# TransistorsArduino.net
KiCad netlist of a schematic drawn in EAGLE
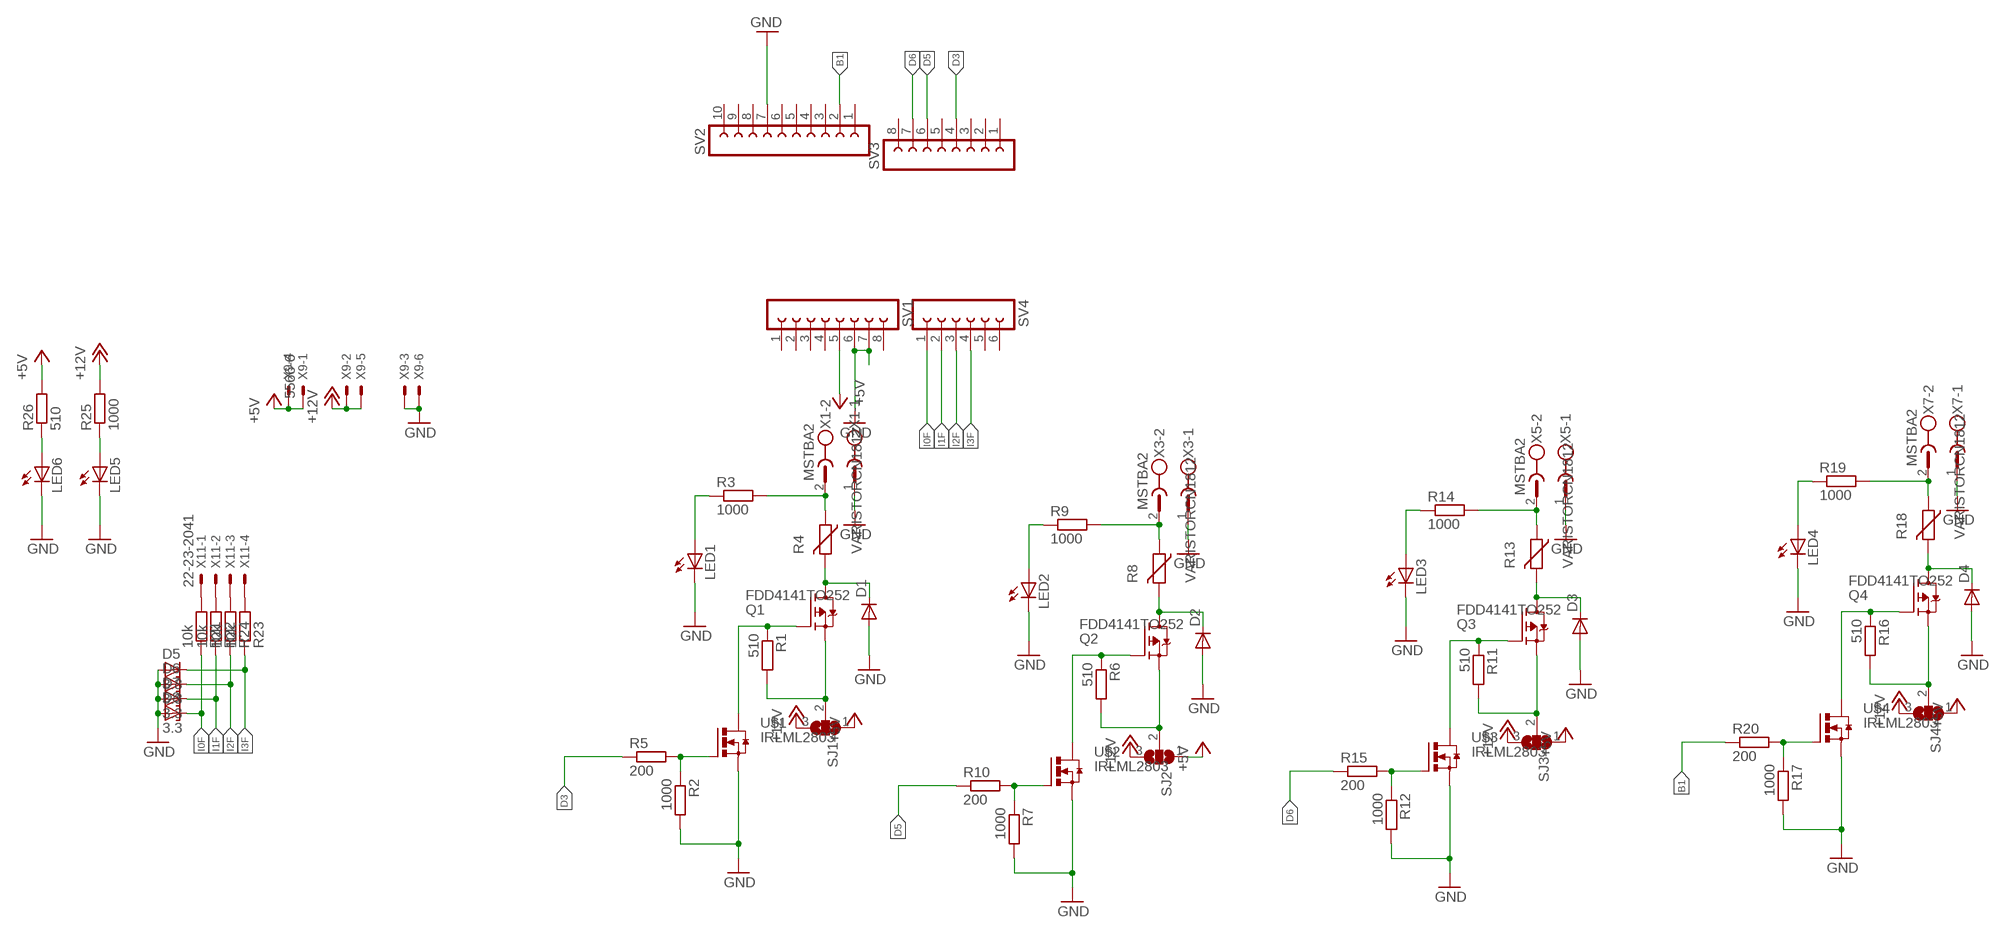
[diagram p0: schematic, sheet 1]

(export (version "E")
  (design (tool "Eeschema 10.0.6"))
  (components
    (comp (ref "D1")
      (value "DIODE-SMB")
      (footprint "eagle-import:SMB")
      (libsource (lib "eagle-import") (part "DIODE-SMB"))
    )
    (comp (ref "D2")
      (value "DIODE-SMB")
      (footprint "eagle-import:SMB")
      (libsource (lib "eagle-import") (part "DIODE-SMB"))
    )
    (comp (ref "D3")
      (value "DIODE-SMB")
      (footprint "eagle-import:SMB")
      (libsource (lib "eagle-import") (part "DIODE-SMB"))
    )
    (comp (ref "D4")
      (value "DIODE-SMB")
      (footprint "eagle-import:SMB")
      (libsource (lib "eagle-import") (part "DIODE-SMB"))
    )
    (comp (ref "D5")
      (value "3.3")
      (footprint "eagle-import:SOD80C")
      (libsource (lib "eagle-import") (part "ZENER-DIODESOD80C"))
    )
    (comp (ref "D6")
      (value "3.3")
      (footprint "eagle-import:SOD80C")
      (libsource (lib "eagle-import") (part "ZENER-DIODESOD80C"))
    )
    (comp (ref "D7")
      (value "3.3")
      (footprint "eagle-import:SOD80C")
      (libsource (lib "eagle-import") (part "ZENER-DIODESOD80C"))
    )
    (comp (ref "D8")
      (value "3.3")
      (footprint "eagle-import:SOD80C")
      (libsource (lib "eagle-import") (part "ZENER-DIODESOD80C"))
    )
    (comp (ref "LED1")
      (value "LEDCHIPLED_1206")
      (footprint "eagle-import:CHIPLED_1206")
      (libsource (lib "eagle-import") (part "LEDCHIPLED_1206"))
    )
    (comp (ref "LED2")
      (value "LEDCHIPLED_1206")
      (footprint "eagle-import:CHIPLED_1206")
      (libsource (lib "eagle-import") (part "LEDCHIPLED_1206"))
    )
    (comp (ref "LED3")
      (value "LEDCHIPLED_1206")
      (footprint "eagle-import:CHIPLED_1206")
      (libsource (lib "eagle-import") (part "LEDCHIPLED_1206"))
    )
    (comp (ref "LED4")
      (value "LEDCHIPLED_1206")
      (footprint "eagle-import:CHIPLED_1206")
      (libsource (lib "eagle-import") (part "LEDCHIPLED_1206"))
    )
    (comp (ref "LED5")
      (value "LEDCHIPLED_1206")
      (footprint "eagle-import:CHIPLED_1206")
      (libsource (lib "eagle-import") (part "LEDCHIPLED_1206"))
    )
    (comp (ref "LED6")
      (value "LEDCHIPLED_1206")
      (footprint "eagle-import:CHIPLED_1206")
      (libsource (lib "eagle-import") (part "LEDCHIPLED_1206"))
    )
    (comp (ref "Q1")
      (value "FDD4141TO252")
      (footprint "eagle-import:TO252")
      (libsource (lib "eagle-import") (part "FDD4141TO252"))
    )
    (comp (ref "Q2")
      (value "FDD4141TO252")
      (footprint "eagle-import:TO252")
      (libsource (lib "eagle-import") (part "FDD4141TO252"))
    )
    (comp (ref "Q3")
      (value "FDD4141TO252")
      (footprint "eagle-import:TO252")
      (libsource (lib "eagle-import") (part "FDD4141TO252"))
    )
    (comp (ref "Q4")
      (value "FDD4141TO252")
      (footprint "eagle-import:TO252")
      (libsource (lib "eagle-import") (part "FDD4141TO252"))
    )
    (comp (ref "R1")
      (value "510")
      (footprint "eagle-import:M0805")
      (libsource (lib "eagle-import") (part "R-EU_M0805"))
    )
    (comp (ref "R2")
      (value "1000")
      (footprint "eagle-import:M0805")
      (libsource (lib "eagle-import") (part "R-EU_M0805"))
    )
    (comp (ref "R3")
      (value "1000")
      (footprint "eagle-import:M0805")
      (libsource (lib "eagle-import") (part "R-EU_M0805"))
    )
    (comp (ref "R4")
      (value "VARISTORCN1812")
      (footprint "eagle-import:CT_CN1812")
      (libsource (lib "eagle-import") (part "VARISTORCN1812"))
    )
    (comp (ref "R5")
      (value "200")
      (footprint "eagle-import:M0805")
      (libsource (lib "eagle-import") (part "R-EU_M0805"))
    )
    (comp (ref "R6")
      (value "510")
      (footprint "eagle-import:M0805")
      (libsource (lib "eagle-import") (part "R-EU_M0805"))
    )
    (comp (ref "R7")
      (value "1000")
      (footprint "eagle-import:M0805")
      (libsource (lib "eagle-import") (part "R-EU_M0805"))
    )
    (comp (ref "R8")
      (value "VARISTORCN1812")
      (footprint "eagle-import:CT_CN1812")
      (libsource (lib "eagle-import") (part "VARISTORCN1812"))
    )
    (comp (ref "R9")
      (value "1000")
      (footprint "eagle-import:M0805")
      (libsource (lib "eagle-import") (part "R-EU_M0805"))
    )
    (comp (ref "R10")
      (value "200")
      (footprint "eagle-import:M0805")
      (libsource (lib "eagle-import") (part "R-EU_M0805"))
    )
    (comp (ref "R11")
      (value "510")
      (footprint "eagle-import:M0805")
      (libsource (lib "eagle-import") (part "R-EU_M0805"))
    )
    (comp (ref "R12")
      (value "1000")
      (footprint "eagle-import:M0805")
      (libsource (lib "eagle-import") (part "R-EU_M0805"))
    )
    (comp (ref "R13")
      (value "VARISTORCN1812")
      (footprint "eagle-import:CT_CN1812")
      (libsource (lib "eagle-import") (part "VARISTORCN1812"))
    )
    (comp (ref "R14")
      (value "1000")
      (footprint "eagle-import:M0805")
      (libsource (lib "eagle-import") (part "R-EU_M0805"))
    )
    (comp (ref "R15")
      (value "200")
      (footprint "eagle-import:M0805")
      (libsource (lib "eagle-import") (part "R-EU_M0805"))
    )
    (comp (ref "R16")
      (value "510")
      (footprint "eagle-import:M0805")
      (libsource (lib "eagle-import") (part "R-EU_M0805"))
    )
    (comp (ref "R17")
      (value "1000")
      (footprint "eagle-import:M0805")
      (libsource (lib "eagle-import") (part "R-EU_M0805"))
    )
    (comp (ref "R18")
      (value "VARISTORCN1812")
      (footprint "eagle-import:CT_CN1812")
      (libsource (lib "eagle-import") (part "VARISTORCN1812"))
    )
    (comp (ref "R19")
      (value "1000")
      (footprint "eagle-import:M0805")
      (libsource (lib "eagle-import") (part "R-EU_M0805"))
    )
    (comp (ref "R20")
      (value "200")
      (footprint "eagle-import:M0805")
      (libsource (lib "eagle-import") (part "R-EU_M0805"))
    )
    (comp (ref "R21")
      (value "10k")
      (footprint "eagle-import:M0805")
      (libsource (lib "eagle-import") (part "R-EU_M0805"))
    )
    (comp (ref "R22")
      (value "10k")
      (footprint "eagle-import:M0805")
      (libsource (lib "eagle-import") (part "R-EU_M0805"))
    )
    (comp (ref "R23")
      (value "10k")
      (footprint "eagle-import:M0805")
      (libsource (lib "eagle-import") (part "R-EU_M0805"))
    )
    (comp (ref "R24")
      (value "10k")
      (footprint "eagle-import:M0805")
      (libsource (lib "eagle-import") (part "R-EU_M0805"))
    )
    (comp (ref "R25")
      (value "1000")
      (footprint "eagle-import:M0805")
      (libsource (lib "eagle-import") (part "R-EU_M0805"))
    )
    (comp (ref "R26")
      (value "510")
      (footprint "eagle-import:M0805")
      (libsource (lib "eagle-import") (part "R-EU_M0805"))
    )
    (comp (ref "SJ1")
      (value "SJ2W")
      (footprint "eagle-import:SJ_2")
      (libsource (lib "eagle-import") (part "SJ2W"))
    )
    (comp (ref "SJ2")
      (value "SJ2W")
      (footprint "eagle-import:SJ_2")
      (libsource (lib "eagle-import") (part "SJ2W"))
    )
    (comp (ref "SJ3")
      (value "SJ2W")
      (footprint "eagle-import:SJ_2")
      (libsource (lib "eagle-import") (part "SJ2W"))
    )
    (comp (ref "SJ4")
      (value "SJ2W")
      (footprint "eagle-import:SJ_2")
      (libsource (lib "eagle-import") (part "SJ2W"))
    )
    (comp (ref "SV1")
      (value "FE08-1")
      (footprint "eagle-import:FE08")
      (libsource (lib "eagle-import") (part "FE08-1"))
    )
    (comp (ref "SV2")
      (value "FE10-1")
      (footprint "eagle-import:FE10")
      (libsource (lib "eagle-import") (part "FE10-1"))
    )
    (comp (ref "SV3")
      (value "FE08-1")
      (footprint "eagle-import:FE08")
      (fields (field (name "OC_FARNELL") "unknown") (field (name "OC_NEWARK") "unknown"))
      (libsource (lib "eagle-import") (part "FE08-1"))
    )
    (comp (ref "SV4")
      (value "FE06-1")
      (footprint "eagle-import:FE06")
      (libsource (lib "eagle-import") (part "FE06-1"))
    )
    (comp (ref "U$1")
      (value "IRLML2803")
      (footprint "eagle-import:SUPER-SOT3")
      (libsource (lib "eagle-import") (part "IRLML2803"))
    )
    (comp (ref "U$2")
      (value "IRLML2803")
      (footprint "eagle-import:SUPER-SOT3")
      (libsource (lib "eagle-import") (part "IRLML2803"))
    )
    (comp (ref "U$3")
      (value "IRLML2803")
      (footprint "eagle-import:SUPER-SOT3")
      (libsource (lib "eagle-import") (part "IRLML2803"))
    )
    (comp (ref "U$4")
      (value "IRLML2803")
      (footprint "eagle-import:SUPER-SOT3")
      (libsource (lib "eagle-import") (part "IRLML2803"))
    )
    (comp (ref "X1")
      (value "MSTBA2")
      (footprint "eagle-import:MSTBA2")
      (fields (field (name "MF") "FARNELL") (field (name "MPN") "1757242"))
      (libsource (lib "eagle-import") (part "MSTBA2"))
    )
    (comp (ref "X3")
      (value "MSTBA2")
      (footprint "eagle-import:MSTBA2")
      (fields (field (name "MF") "FARNELL") (field (name "MPN") "1757242"))
      (libsource (lib "eagle-import") (part "MSTBA2"))
    )
    (comp (ref "X5")
      (value "MSTBA2")
      (footprint "eagle-import:MSTBA2")
      (fields (field (name "MF") "FARNELL") (field (name "MPN") "1757242"))
      (libsource (lib "eagle-import") (part "MSTBA2"))
    )
    (comp (ref "X7")
      (value "MSTBA2")
      (footprint "eagle-import:MSTBA2")
      (fields (field (name "MF") "FARNELL") (field (name "MPN") "1757242"))
      (libsource (lib "eagle-import") (part "MSTBA2"))
    )
    (comp (ref "X9")
      (value "5566-6")
      (footprint "eagle-import:5566-6")
      (fields (field (name "MPN") "95566-61002"))
      (libsource (lib "eagle-import") (part "5566-6"))
    )
    (comp (ref "X11")
      (value "22-23-2041")
      (footprint "eagle-import:22-23-2041")
      (fields
        (field (name "MF") "MOLEX")
        (field (name "MF_1") "MOLEX")
        (field (name "MPN") "22-23-2041")
        (field (name "OC_FARNELL") "1462920")
        (field (name "OC_NEWARK") "38C0355")
      )
      (libsource (lib "eagle-import") (part "22-23-2041"))
    )
  )
  (nets
    (net (code "1") (name "+5V") (class "Default")
      (node (ref "R26") (pin "2") (pinfunction "2_2") (pintype "passive"))
      (node (ref "SJ1") (pin "1") (pinfunction "1_1") (pintype "passive"))
      (node (ref "SJ2") (pin "1") (pinfunction "1_1") (pintype "passive"))
      (node (ref "SJ3") (pin "1") (pinfunction "1_1") (pintype "passive"))
      (node (ref "SJ4") (pin "1") (pinfunction "1_1") (pintype "passive"))
      (node (ref "SV1") (pin "5") (pinfunction "5_5") (pintype "passive"))
      (node (ref "X9") (pin "1") (pinfunction "S_1") (pintype "passive"))
      (node (ref "X9") (pin "4") (pinfunction "S_4") (pintype "passive"))
    )
    (net (code "2") (name "+12V") (class "Default")
      (node (ref "R25") (pin "2") (pinfunction "2_2") (pintype "passive"))
      (node (ref "SJ1") (pin "3") (pinfunction "3_3") (pintype "passive"))
      (node (ref "SJ2") (pin "3") (pinfunction "3_3") (pintype "passive"))
      (node (ref "SJ3") (pin "3") (pinfunction "3_3") (pintype "passive"))
      (node (ref "SJ4") (pin "3") (pinfunction "3_3") (pintype "passive"))
      (node (ref "X9") (pin "2") (pinfunction "S_2") (pintype "passive"))
      (node (ref "X9") (pin "5") (pinfunction "S_5") (pintype "passive"))
    )
    (net (code "3") (name "B1") (class "Default")
      (node (ref "R20") (pin "1") (pinfunction "1_1") (pintype "passive"))
      (node (ref "SV2") (pin "2") (pinfunction "2_2") (pintype "passive"))
    )
    (net (code "4") (name "D3") (class "Default")
      (node (ref "R5") (pin "1") (pinfunction "1_1") (pintype "passive"))
      (node (ref "SV3") (pin "4") (pinfunction "4_4") (pintype "passive"))
    )
    (net (code "5") (name "D5") (class "Default")
      (node (ref "R10") (pin "1") (pinfunction "1_1") (pintype "passive"))
      (node (ref "SV3") (pin "6") (pinfunction "6_6") (pintype "passive"))
    )
    (net (code "6") (name "D6") (class "Default")
      (node (ref "R15") (pin "1") (pinfunction "1_1") (pintype "passive"))
      (node (ref "SV3") (pin "7") (pinfunction "7_7") (pintype "passive"))
    )
    (net (code "7") (name "GND") (class "Default")
      (node (ref "D1") (pin "A") (pinfunction "A_A") (pintype "passive"))
      (node (ref "D2") (pin "A") (pinfunction "A_A") (pintype "passive"))
      (node (ref "D3") (pin "A") (pinfunction "A_A") (pintype "passive"))
      (node (ref "D4") (pin "A") (pinfunction "A_A") (pintype "passive"))
      (node (ref "D5") (pin "A") (pinfunction "A_A") (pintype "passive"))
      (node (ref "D6") (pin "A") (pinfunction "A_A") (pintype "passive"))
      (node (ref "D7") (pin "A") (pinfunction "A_A") (pintype "passive"))
      (node (ref "D8") (pin "A") (pinfunction "A_A") (pintype "passive"))
      (node (ref "LED1") (pin "C") (pinfunction "C_C") (pintype "passive"))
      (node (ref "LED2") (pin "C") (pinfunction "C_C") (pintype "passive"))
      (node (ref "LED3") (pin "C") (pinfunction "C_C") (pintype "passive"))
      (node (ref "LED4") (pin "C") (pinfunction "C_C") (pintype "passive"))
      (node (ref "LED5") (pin "C") (pinfunction "C_C") (pintype "passive"))
      (node (ref "LED6") (pin "C") (pinfunction "C_C") (pintype "passive"))
      (node (ref "R12") (pin "2") (pinfunction "2_2") (pintype "passive"))
      (node (ref "R17") (pin "2") (pinfunction "2_2") (pintype "passive"))
      (node (ref "R2") (pin "2") (pinfunction "2_2") (pintype "passive"))
      (node (ref "R7") (pin "2") (pinfunction "2_2") (pintype "passive"))
      (node (ref "SV1") (pin "6") (pinfunction "6_6") (pintype "passive"))
      (node (ref "SV1") (pin "7") (pinfunction "7_7") (pintype "passive"))
      (node (ref "SV2") (pin "7") (pinfunction "7_7") (pintype "passive"))
      (node (ref "U$1") (pin "2") (pinfunction "S_2") (pintype "passive"))
      (node (ref "U$2") (pin "2") (pinfunction "S_2") (pintype "passive"))
      (node (ref "U$3") (pin "2") (pinfunction "S_2") (pintype "passive"))
      (node (ref "U$4") (pin "2") (pinfunction "S_2") (pintype "passive"))
      (node (ref "X1") (pin "1") (pinfunction "1_1") (pintype "passive"))
      (node (ref "X3") (pin "1") (pinfunction "1_1") (pintype "passive"))
      (node (ref "X5") (pin "1") (pinfunction "1_1") (pintype "passive"))
      (node (ref "X7") (pin "1") (pinfunction "1_1") (pintype "passive"))
      (node (ref "X9") (pin "3") (pinfunction "S_3") (pintype "passive"))
      (node (ref "X9") (pin "6") (pinfunction "S_6") (pintype "passive"))
    )
    (net (code "8") (name "I0F") (class "Default")
      (node (ref "D8") (pin "C") (pinfunction "C_C") (pintype "passive"))
      (node (ref "R21") (pin "1") (pinfunction "1_1") (pintype "passive"))
      (node (ref "SV4") (pin "1") (pinfunction "1_1") (pintype "passive"))
    )
    (net (code "9") (name "I1F") (class "Default")
      (node (ref "D7") (pin "C") (pinfunction "C_C") (pintype "passive"))
      (node (ref "R22") (pin "1") (pinfunction "1_1") (pintype "passive"))
      (node (ref "SV4") (pin "2") (pinfunction "2_2") (pintype "passive"))
    )
    (net (code "10") (name "I2F") (class "Default")
      (node (ref "D6") (pin "C") (pinfunction "C_C") (pintype "passive"))
      (node (ref "R24") (pin "1") (pinfunction "1_1") (pintype "passive"))
      (node (ref "SV4") (pin "3") (pinfunction "3_3") (pintype "passive"))
    )
    (net (code "11") (name "I3F") (class "Default")
      (node (ref "D5") (pin "C") (pinfunction "C_C") (pintype "passive"))
      (node (ref "R23") (pin "1") (pinfunction "1_1") (pintype "passive"))
      (node (ref "SV4") (pin "4") (pinfunction "4_4") (pintype "passive"))
    )
    (net (code "12") (name "Net-(LED1-PadA)") (class "Default")
      (node (ref "LED1") (pin "A") (pinfunction "A_A") (pintype "passive"))
      (node (ref "R3") (pin "1") (pinfunction "1_1") (pintype "passive"))
    )
    (net (code "13") (name "Net-(LED2-PadA)") (class "Default")
      (node (ref "LED2") (pin "A") (pinfunction "A_A") (pintype "passive"))
      (node (ref "R9") (pin "1") (pinfunction "1_1") (pintype "passive"))
    )
    (net (code "14") (name "Net-(LED3-PadA)") (class "Default")
      (node (ref "LED3") (pin "A") (pinfunction "A_A") (pintype "passive"))
      (node (ref "R14") (pin "1") (pinfunction "1_1") (pintype "passive"))
    )
    (net (code "15") (name "Net-(LED4-PadA)") (class "Default")
      (node (ref "LED4") (pin "A") (pinfunction "A_A") (pintype "passive"))
      (node (ref "R19") (pin "1") (pinfunction "1_1") (pintype "passive"))
    )
    (net (code "16") (name "Net-(LED5-PadA)") (class "Default")
      (node (ref "LED5") (pin "A") (pinfunction "A_A") (pintype "passive"))
      (node (ref "R25") (pin "1") (pinfunction "1_1") (pintype "passive"))
    )
    (net (code "17") (name "Net-(LED6-PadA)") (class "Default")
      (node (ref "LED6") (pin "A") (pinfunction "A_A") (pintype "passive"))
      (node (ref "R26") (pin "1") (pinfunction "1_1") (pintype "passive"))
    )
    (net (code "18") (name "Net-(Q1-D)") (class "Default")
      (node (ref "D1") (pin "C") (pinfunction "C_C") (pintype "passive"))
      (node (ref "Q1") (pin "3") (pinfunction "D_3") (pintype "passive"))
      (node (ref "R4") (pin "2") (pinfunction "2_2") (pintype "passive"))
    )
    (net (code "19") (name "Net-(Q1-G)") (class "Default")
      (node (ref "Q1") (pin "1") (pinfunction "G_1") (pintype "passive"))
      (node (ref "R1") (pin "1") (pinfunction "1_1") (pintype "passive"))
      (node (ref "U$1") (pin "3") (pinfunction "D_3") (pintype "passive"))
    )
    (net (code "20") (name "Net-(Q1-S)") (class "Default")
      (node (ref "Q1") (pin "2") (pinfunction "S_2") (pintype "passive"))
      (node (ref "R1") (pin "2") (pinfunction "2_2") (pintype "passive"))
      (node (ref "SJ1") (pin "2") (pinfunction "2_2") (pintype "passive"))
    )
    (net (code "21") (name "Net-(Q2-D)") (class "Default")
      (node (ref "D2") (pin "C") (pinfunction "C_C") (pintype "passive"))
      (node (ref "Q2") (pin "3") (pinfunction "D_3") (pintype "passive"))
      (node (ref "R8") (pin "2") (pinfunction "2_2") (pintype "passive"))
    )
    (net (code "22") (name "Net-(Q2-G)") (class "Default")
      (node (ref "Q2") (pin "1") (pinfunction "G_1") (pintype "passive"))
      (node (ref "R6") (pin "1") (pinfunction "1_1") (pintype "passive"))
      (node (ref "U$2") (pin "3") (pinfunction "D_3") (pintype "passive"))
    )
    (net (code "23") (name "Net-(Q2-S)") (class "Default")
      (node (ref "Q2") (pin "2") (pinfunction "S_2") (pintype "passive"))
      (node (ref "R6") (pin "2") (pinfunction "2_2") (pintype "passive"))
      (node (ref "SJ2") (pin "2") (pinfunction "2_2") (pintype "passive"))
    )
    (net (code "24") (name "Net-(Q3-D)") (class "Default")
      (node (ref "D3") (pin "C") (pinfunction "C_C") (pintype "passive"))
      (node (ref "Q3") (pin "3") (pinfunction "D_3") (pintype "passive"))
      (node (ref "R13") (pin "2") (pinfunction "2_2") (pintype "passive"))
    )
    (net (code "25") (name "Net-(Q3-G)") (class "Default")
      (node (ref "Q3") (pin "1") (pinfunction "G_1") (pintype "passive"))
      (node (ref "R11") (pin "1") (pinfunction "1_1") (pintype "passive"))
      (node (ref "U$3") (pin "3") (pinfunction "D_3") (pintype "passive"))
    )
    (net (code "26") (name "Net-(Q3-S)") (class "Default")
      (node (ref "Q3") (pin "2") (pinfunction "S_2") (pintype "passive"))
      (node (ref "R11") (pin "2") (pinfunction "2_2") (pintype "passive"))
      (node (ref "SJ3") (pin "2") (pinfunction "2_2") (pintype "passive"))
    )
    (net (code "27") (name "Net-(Q4-D)") (class "Default")
      (node (ref "D4") (pin "C") (pinfunction "C_C") (pintype "passive"))
      (node (ref "Q4") (pin "3") (pinfunction "D_3") (pintype "passive"))
      (node (ref "R18") (pin "2") (pinfunction "2_2") (pintype "passive"))
    )
    (net (code "28") (name "Net-(Q4-G)") (class "Default")
      (node (ref "Q4") (pin "1") (pinfunction "G_1") (pintype "passive"))
      (node (ref "R16") (pin "1") (pinfunction "1_1") (pintype "passive"))
      (node (ref "U$4") (pin "3") (pinfunction "D_3") (pintype "passive"))
    )
    (net (code "29") (name "Net-(Q4-S)") (class "Default")
      (node (ref "Q4") (pin "2") (pinfunction "S_2") (pintype "passive"))
      (node (ref "R16") (pin "2") (pinfunction "2_2") (pintype "passive"))
      (node (ref "SJ4") (pin "2") (pinfunction "2_2") (pintype "passive"))
    )
    (net (code "30") (name "Net-(U$1-G)") (class "Default")
      (node (ref "R2") (pin "1") (pinfunction "1_1") (pintype "passive"))
      (node (ref "R5") (pin "2") (pinfunction "2_2") (pintype "passive"))
      (node (ref "U$1") (pin "1") (pinfunction "G_1") (pintype "passive"))
    )
    (net (code "31") (name "Net-(U$2-G)") (class "Default")
      (node (ref "R10") (pin "2") (pinfunction "2_2") (pintype "passive"))
      (node (ref "R7") (pin "1") (pinfunction "1_1") (pintype "passive"))
      (node (ref "U$2") (pin "1") (pinfunction "G_1") (pintype "passive"))
    )
    (net (code "32") (name "Net-(U$3-G)") (class "Default")
      (node (ref "R12") (pin "1") (pinfunction "1_1") (pintype "passive"))
      (node (ref "R15") (pin "2") (pinfunction "2_2") (pintype "passive"))
      (node (ref "U$3") (pin "1") (pinfunction "G_1") (pintype "passive"))
    )
    (net (code "33") (name "Net-(U$4-G)") (class "Default")
      (node (ref "R17") (pin "1") (pinfunction "1_1") (pintype "passive"))
      (node (ref "R20") (pin "2") (pinfunction "2_2") (pintype "passive"))
      (node (ref "U$4") (pin "1") (pinfunction "G_1") (pintype "passive"))
    )
    (net (code "34") (name "Net-(X1B-1)") (class "Default")
      (node (ref "R3") (pin "2") (pinfunction "2_2") (pintype "passive"))
      (node (ref "R4") (pin "1") (pinfunction "1_1") (pintype "passive"))
      (node (ref "X1") (pin "2") (pinfunction "1_2") (pintype "passive"))
    )
    (net (code "35") (name "Net-(X3B-1)") (class "Default")
      (node (ref "R8") (pin "1") (pinfunction "1_1") (pintype "passive"))
      (node (ref "R9") (pin "2") (pinfunction "2_2") (pintype "passive"))
      (node (ref "X3") (pin "2") (pinfunction "1_2") (pintype "passive"))
    )
    (net (code "36") (name "Net-(X5B-1)") (class "Default")
      (node (ref "R13") (pin "1") (pinfunction "1_1") (pintype "passive"))
      (node (ref "R14") (pin "2") (pinfunction "2_2") (pintype "passive"))
      (node (ref "X5") (pin "2") (pinfunction "1_2") (pintype "passive"))
    )
    (net (code "37") (name "Net-(X7B-1)") (class "Default")
      (node (ref "R18") (pin "1") (pinfunction "1_1") (pintype "passive"))
      (node (ref "R19") (pin "2") (pinfunction "2_2") (pintype "passive"))
      (node (ref "X7") (pin "2") (pinfunction "1_2") (pintype "passive"))
    )
    (net (code "38") (name "Net-(X11A-S)") (class "Default")
      (node (ref "R21") (pin "2") (pinfunction "2_2") (pintype "passive"))
      (node (ref "X11") (pin "1") (pinfunction "S_1") (pintype "passive"))
    )
    (net (code "39") (name "Net-(X11B-S)") (class "Default")
      (node (ref "R22") (pin "2") (pinfunction "2_2") (pintype "passive"))
      (node (ref "X11") (pin "2") (pinfunction "S_2") (pintype "passive"))
    )
    (net (code "40") (name "Net-(X11C-S)") (class "Default")
      (node (ref "R24") (pin "2") (pinfunction "2_2") (pintype "passive"))
      (node (ref "X11") (pin "3") (pinfunction "S_3") (pintype "passive"))
    )
    (net (code "41") (name "Net-(X11D-S)") (class "Default")
      (node (ref "R23") (pin "2") (pinfunction "2_2") (pintype "passive"))
      (node (ref "X11") (pin "4") (pinfunction "S_4") (pintype "passive"))
    )
    (net (code "42") (name "unconnected-(SV1-Pad1)") (class "Default")
      (node (ref "SV1") (pin "1") (pinfunction "1_1") (pintype "passive"))
    )
    (net (code "43") (name "unconnected-(SV1-Pad2)") (class "Default")
      (node (ref "SV1") (pin "2") (pinfunction "2_2") (pintype "passive"))
    )
    (net (code "44") (name "unconnected-(SV1-Pad3)") (class "Default")
      (node (ref "SV1") (pin "3") (pinfunction "3_3") (pintype "passive"))
    )
    (net (code "45") (name "unconnected-(SV1-Pad4)") (class "Default")
      (node (ref "SV1") (pin "4") (pinfunction "4_4") (pintype "passive"))
    )
    (net (code "46") (name "unconnected-(SV1-Pad8)") (class "Default")
      (node (ref "SV1") (pin "8") (pinfunction "8_8") (pintype "passive"))
    )
    (net (code "47") (name "unconnected-(SV2-Pad1)") (class "Default")
      (node (ref "SV2") (pin "1") (pinfunction "1_1") (pintype "passive"))
    )
    (net (code "48") (name "unconnected-(SV2-Pad3)") (class "Default")
      (node (ref "SV2") (pin "3") (pinfunction "3_3") (pintype "passive"))
    )
    (net (code "49") (name "unconnected-(SV2-Pad4)") (class "Default")
      (node (ref "SV2") (pin "4") (pinfunction "4_4") (pintype "passive"))
    )
    (net (code "50") (name "unconnected-(SV2-Pad5)") (class "Default")
      (node (ref "SV2") (pin "5") (pinfunction "5_5") (pintype "passive"))
    )
    (net (code "51") (name "unconnected-(SV2-Pad6)") (class "Default")
      (node (ref "SV2") (pin "6") (pinfunction "6_6") (pintype "passive"))
    )
    (net (code "52") (name "unconnected-(SV2-Pad8)") (class "Default")
      (node (ref "SV2") (pin "8") (pinfunction "8_8") (pintype "passive"))
    )
    (net (code "53") (name "unconnected-(SV2-Pad9)") (class "Default")
      (node (ref "SV2") (pin "9") (pinfunction "9_9") (pintype "passive"))
    )
    (net (code "54") (name "unconnected-(SV2-Pad10)") (class "Default")
      (node (ref "SV2") (pin "10") (pinfunction "10_10") (pintype "passive"))
    )
    (net (code "55") (name "unconnected-(SV3-Pad1)") (class "Default")
      (node (ref "SV3") (pin "1") (pinfunction "1_1") (pintype "passive"))
    )
    (net (code "56") (name "unconnected-(SV3-Pad2)") (class "Default")
      (node (ref "SV3") (pin "2") (pinfunction "2_2") (pintype "passive"))
    )
    (net (code "57") (name "unconnected-(SV3-Pad3)") (class "Default")
      (node (ref "SV3") (pin "3") (pinfunction "3_3") (pintype "passive"))
    )
    (net (code "58") (name "unconnected-(SV3-Pad5)") (class "Default")
      (node (ref "SV3") (pin "5") (pinfunction "5_5") (pintype "passive"))
    )
    (net (code "59") (name "unconnected-(SV3-Pad8)") (class "Default")
      (node (ref "SV3") (pin "8") (pinfunction "8_8") (pintype "passive"))
    )
    (net (code "60") (name "unconnected-(SV4-Pad5)") (class "Default")
      (node (ref "SV4") (pin "5") (pinfunction "5_5") (pintype "passive"))
    )
    (net (code "61") (name "unconnected-(SV4-Pad6)") (class "Default")
      (node (ref "SV4") (pin "6") (pinfunction "6_6") (pintype "passive"))
    )
  )
)
